# PCB-PWR-CON2.net
KiCad netlist of a schematic drawn in EAGLE
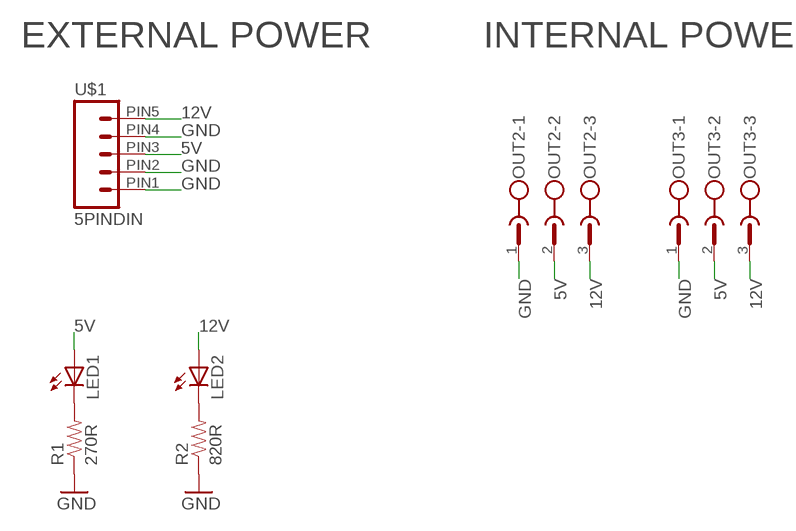
[diagram p0: schematic, sheet 1]

(export (version "E")
  (design (tool "Eeschema 10.0.6"))
  (components
    (comp (ref "LED1")
      (value "LED3MM")
      (footprint "eagle-import:LED3MM")
      (libsource (lib "eagle-import") (part "LED3MM"))
    )
    (comp (ref "LED2")
      (value "LED3MM")
      (footprint "eagle-import:LED3MM")
      (libsource (lib "eagle-import") (part "LED3MM"))
    )
    (comp (ref "OUT2")
      (value "CON1")
      (footprint "eagle-import:MSTBV3")
      (fields (field (name "MPN") "MSTBV 2,5/3-GF-5.08"))
      (libsource (lib "eagle-import") (part "MSTBV3"))
    )
    (comp (ref "OUT3")
      (value "CON1")
      (footprint "eagle-import:MSTBV3")
      (fields (field (name "MPN") "MSTBV 2,5/3-GF-5.08"))
      (libsource (lib "eagle-import") (part "MSTBV3"))
    )
    (comp (ref "R1")
      (value "270R")
      (footprint "eagle-import:0603-RES")
      (libsource (lib "eagle-import") (part "RESISTOR0603-RES"))
    )
    (comp (ref "R2")
      (value "820R")
      (footprint "eagle-import:0603-RES")
      (libsource (lib "eagle-import") (part "RESISTOR0603-RES"))
    )
    (comp (ref "U$1")
      (value "5PINDIN")
      (footprint "eagle-import:5PINDIN")
      (libsource (lib "eagle-import") (part "5PINDIN"))
    )
  )
  (nets
    (net (code "1") (name "/5V") (class "Default")
      (node (ref "LED1") (pin "A") (pinfunction "A_A") (pintype "passive"))
      (node (ref "OUT2") (pin "2") (pinfunction "1_2") (pintype "passive"))
      (node (ref "OUT3") (pin "2") (pinfunction "1_2") (pintype "passive"))
      (node (ref "U$1") (pin "PIN3") (pinfunction "3_PIN3") (pintype "passive"))
    )
    (net (code "2") (name "/12V") (class "Default")
      (node (ref "LED2") (pin "A") (pinfunction "A_A") (pintype "passive"))
      (node (ref "OUT2") (pin "3") (pinfunction "1_3") (pintype "passive"))
      (node (ref "OUT3") (pin "3") (pinfunction "1_3") (pintype "passive"))
      (node (ref "U$1") (pin "PIN5") (pinfunction "5_PIN5") (pintype "passive"))
    )
    (net (code "3") (name "GND") (class "Default")
      (node (ref "OUT2") (pin "1") (pinfunction "1_1") (pintype "passive"))
      (node (ref "OUT3") (pin "1") (pinfunction "1_1") (pintype "passive"))
      (node (ref "R1") (pin "1") (pinfunction "1_1") (pintype "passive"))
      (node (ref "R2") (pin "1") (pinfunction "1_1") (pintype "passive"))
      (node (ref "U$1") (pin "PIN1") (pinfunction "1_PIN1") (pintype "passive"))
      (node (ref "U$1") (pin "PIN2") (pinfunction "2_PIN2") (pintype "passive"))
      (node (ref "U$1") (pin "PIN4") (pinfunction "4_PIN4") (pintype "passive"))
    )
    (net (code "4") (name "Net-(LED1-C)") (class "Default")
      (node (ref "LED1") (pin "K") (pinfunction "C_K") (pintype "passive"))
      (node (ref "R1") (pin "2") (pinfunction "2_2") (pintype "passive"))
    )
    (net (code "5") (name "Net-(LED2-C)") (class "Default")
      (node (ref "LED2") (pin "K") (pinfunction "C_K") (pintype "passive"))
      (node (ref "R2") (pin "2") (pinfunction "2_2") (pintype "passive"))
    )
  )
)
